# LM5116.net
KiCad netlist of a schematic drawn in Altium Designer
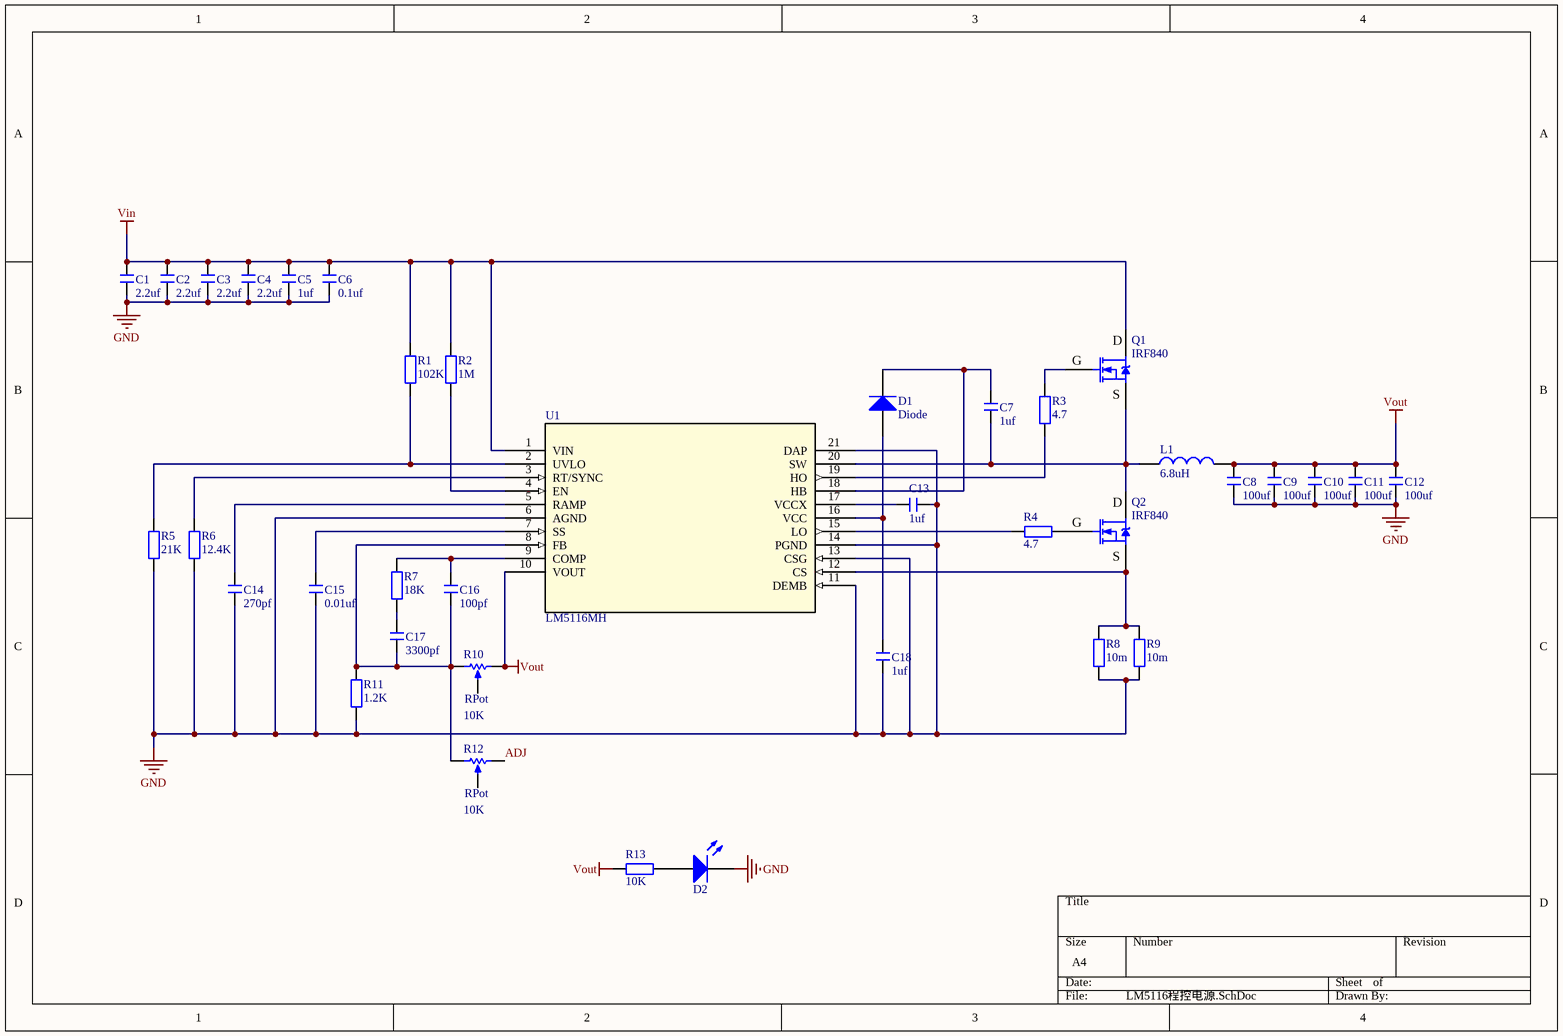
[diagram p0: LM5116程控电源.SchDoc]

(export (version "E")
  (design (tool "Eeschema 10.0.6"))
  (components
    (comp (ref "C1")
      (value "2.2uf")
      (footprint "C 1812_L")
      (description "贴片电容")
      (libsource (lib "0.1 - 电阻-电容-电感") (part "C"))
    )
    (comp (ref "C2")
      (value "2.2uf")
      (footprint "C 1812_L")
      (description "贴片电容")
      (libsource (lib "0.1 - 电阻-电容-电感") (part "C"))
    )
    (comp (ref "C3")
      (value "2.2uf")
      (footprint "C 1812_L")
      (description "贴片电容")
      (libsource (lib "0.1 - 电阻-电容-电感") (part "C"))
    )
    (comp (ref "C4")
      (value "2.2uf")
      (footprint "C 1812_L")
      (description "贴片电容")
      (libsource (lib "0.1 - 电阻-电容-电感") (part "C"))
    )
    (comp (ref "C5")
      (value "1uf")
      (footprint "C 1210_L")
      (description "贴片电容")
      (libsource (lib "0.1 - 电阻-电容-电感") (part "C"))
    )
    (comp (ref "C6")
      (value "0.1uf")
      (footprint "C 0805_L")
      (description "贴片电容")
      (libsource (lib "0.1 - 电阻-电容-电感") (part "C"))
    )
    (comp (ref "C7")
      (value "1uf")
      (footprint "C 0805_L")
      (description "贴片电容")
      (libsource (lib "0.1 - 电阻-电容-电感") (part "C"))
    )
    (comp (ref "C8")
      (value "100uf")
      (footprint "C 1812_L")
      (description "贴片电容")
      (libsource (lib "0.1 - 电阻-电容-电感") (part "C"))
    )
    (comp (ref "C9")
      (value "100uf")
      (footprint "C 1812_L")
      (description "贴片电容")
      (libsource (lib "0.1 - 电阻-电容-电感") (part "C"))
    )
    (comp (ref "C10")
      (value "100uf")
      (footprint "C 1812_L")
      (description "贴片电容")
      (libsource (lib "0.1 - 电阻-电容-电感") (part "C"))
    )
    (comp (ref "C11")
      (value "100uf")
      (footprint "C 1812_L")
      (description "贴片电容")
      (libsource (lib "0.1 - 电阻-电容-电感") (part "C"))
    )
    (comp (ref "C12")
      (value "100uf")
      (footprint "C 1812_L")
      (description "贴片电容")
      (libsource (lib "0.1 - 电阻-电容-电感") (part "C"))
    )
    (comp (ref "C13")
      (value "1uf")
      (footprint "C 0805_L")
      (description "贴片电容")
      (libsource (lib "0.1 - 电阻-电容-电感") (part "C"))
    )
    (comp (ref "C14")
      (value "270pf")
      (footprint "C 0603_L")
      (description "贴片电容")
      (libsource (lib "0.1 - 电阻-电容-电感") (part "C"))
    )
    (comp (ref "C15")
      (value "0.01uf")
      (footprint "C 0603_L")
      (description "贴片电容")
      (libsource (lib "0.1 - 电阻-电容-电感") (part "C"))
    )
    (comp (ref "C16")
      (value "100pf")
      (footprint "C 0603_L")
      (description "贴片电容")
      (libsource (lib "0.1 - 电阻-电容-电感") (part "C"))
    )
    (comp (ref "C17")
      (value "3300pf")
      (footprint "C 0603_L")
      (description "贴片电容")
      (libsource (lib "0.1 - 电阻-电容-电感") (part "C"))
    )
    (comp (ref "C18")
      (value "1uf")
      (footprint "C 0805_L")
      (description "贴片电容")
      (libsource (lib "0.1 - 电阻-电容-电感") (part "C"))
    )
    (comp (ref "D1")
      (value "Diode")
      (footprint "1.30-二极管-整流桥堆:SOD-323")
      (description "Default Diode")
      (fields (field (name "PUBLISHER") "Altium Limited"))
      (libsource (lib "Miscellaneous Devices") (part "Diode"))
    )
    (comp (ref "D2")
      (value "LED")
      (footprint "LED 0603G")
      (description "发光二极管")
      (libsource (lib "0.3 - LED发光二极管") (part "LED"))
    )
    (comp (ref "L1")
      (value "6.8uH")
      (footprint "IND-SMD_L12.6-W12.6_MS1350-XX")
      (description "小功率贴片电感")
      (libsource (lib "0.1 - 电阻-电容-电感") (part "L"))
    )
    (comp (ref "Q1")
      (value "IRF840")
      (footprint "SOT669")
      (description "N沟场效应管")
      (libsource (lib "0.5 - 场效应管-可控硅") (part "IRF840"))
    )
    (comp (ref "Q2")
      (value "IRF840")
      (footprint "SOT669")
      (description "N沟场效应管")
      (libsource (lib "0.5 - 场效应管-可控硅") (part "IRF840"))
    )
    (comp (ref "R1")
      (value "102K")
      (footprint "R 0603_L")
      (description "贴片电阻")
      (fields (field (name "版权归属") "来自淘宝 ID：黄晶宝石"))
      (libsource (lib "0.1 - 电阻-电容-电感") (part "R"))
    )
    (comp (ref "R2")
      (value "1M")
      (footprint "R 0603_L")
      (description "贴片电阻")
      (fields (field (name "版权归属") "来自淘宝 ID：黄晶宝石"))
      (libsource (lib "0.1 - 电阻-电容-电感") (part "R"))
    )
    (comp (ref "R3")
      (value "4.7")
      (footprint "R 0603_L")
      (description "贴片电阻")
      (fields (field (name "版权归属") "来自淘宝 ID：黄晶宝石"))
      (libsource (lib "0.1 - 电阻-电容-电感") (part "R"))
    )
    (comp (ref "R4")
      (value "4.7")
      (footprint "R 0603_L")
      (description "贴片电阻")
      (fields (field (name "版权归属") "来自淘宝 ID：黄晶宝石"))
      (libsource (lib "0.1 - 电阻-电容-电感") (part "R"))
    )
    (comp (ref "R5")
      (value "21K")
      (footprint "R 0603_L")
      (description "贴片电阻")
      (fields (field (name "版权归属") "来自淘宝 ID：黄晶宝石"))
      (libsource (lib "0.1 - 电阻-电容-电感") (part "R"))
    )
    (comp (ref "R6")
      (value "12.4K")
      (footprint "R 0603_L")
      (description "贴片电阻")
      (fields (field (name "版权归属") "来自淘宝 ID：黄晶宝石"))
      (libsource (lib "0.1 - 电阻-电容-电感") (part "R"))
    )
    (comp (ref "R7")
      (value "18K")
      (footprint "R 0603_L")
      (description "贴片电阻")
      (fields (field (name "版权归属") "来自淘宝 ID：黄晶宝石"))
      (libsource (lib "0.1 - 电阻-电容-电感") (part "R"))
    )
    (comp (ref "R8")
      (value "10m")
      (footprint "R 0805_L")
      (description "贴片电阻")
      (fields (field (name "版权归属") "来自淘宝 ID：黄晶宝石"))
      (libsource (lib "0.1 - 电阻-电容-电感") (part "R"))
    )
    (comp (ref "R9")
      (value "10m")
      (footprint "R 0805_L")
      (description "贴片电阻")
      (fields (field (name "版权归属") "来自淘宝 ID：黄晶宝石"))
      (libsource (lib "0.1 - 电阻-电容-电感") (part "R"))
    )
    (comp (ref "R10")
      (value "RPot")
      (footprint "RES-ADJ-SMD_3P-L3.8-W3.6-P1.90-BL")
      (description "Potentiometer")
      (fields (field (name "ALTIUM_VALUE") "10K") (field (name "PUBLISHER") "Altium Limited"))
      (libsource (lib "Miscellaneous Devices") (part "RPot"))
    )
    (comp (ref "R11")
      (value "1.2K")
      (footprint "R 0603_L")
      (description "贴片电阻")
      (fields (field (name "版权归属") "来自淘宝 ID：黄晶宝石"))
      (libsource (lib "0.1 - 电阻-电容-电感") (part "R"))
    )
    (comp (ref "R12")
      (value "RPot")
      (footprint "RES-ADJ-SMD_3P-L3.8-W3.6-P1.90-BL")
      (description "Potentiometer")
      (fields (field (name "ALTIUM_VALUE") "10K") (field (name "PUBLISHER") "Altium Limited"))
      (libsource (lib "Miscellaneous Devices") (part "RPot"))
    )
    (comp (ref "R13")
      (value "10K")
      (footprint "R 0603_L")
      (description "贴片电阻")
      (fields (field (name "版权归属") "来自淘宝 ID：黄晶宝石"))
      (libsource (lib "0.1 - 电阻-电容-电感") (part "R"))
    )
    (comp (ref "U1")
      (value "LM5116MH")
      (footprint "HTSSOP-20_L6.5-W4.4-P0.65-LS6.4-BL-EP")
      (description "No Description Available")
      (fields (field (name "COPYRIGHT") "Copyright (C) 2024 Ultra Librarian. All rights reserved."))
      (libsource (lib "LM5116MH") (part "LM5116MH"))
    )
  )
  (nets
    (net (code "1") (name "/ADJ") (class "Default")
      (node (ref "R12") (pin "2") (pinfunction "BOT_2") (pintype "passive"))
    )
    (net (code "2") (name "GND") (class "Default")
      (node (ref "C1") (pin "1") (pinfunction "1_1") (pintype "passive"))
      (node (ref "C10") (pin "1") (pinfunction "1_1") (pintype "passive"))
      (node (ref "C11") (pin "1") (pinfunction "1_1") (pintype "passive"))
      (node (ref "C12") (pin "1") (pinfunction "1_1") (pintype "passive"))
      (node (ref "C13") (pin "1") (pinfunction "1_1") (pintype "passive"))
      (node (ref "C14") (pin "1") (pinfunction "1_1") (pintype "passive"))
      (node (ref "C15") (pin "1") (pinfunction "1_1") (pintype "passive"))
      (node (ref "C18") (pin "1") (pinfunction "1_1") (pintype "passive"))
      (node (ref "C2") (pin "1") (pinfunction "1_1") (pintype "passive"))
      (node (ref "C3") (pin "1") (pinfunction "1_1") (pintype "passive"))
      (node (ref "C4") (pin "1") (pinfunction "1_1") (pintype "passive"))
      (node (ref "C5") (pin "1") (pinfunction "1_1") (pintype "passive"))
      (node (ref "C6") (pin "1") (pinfunction "1_1") (pintype "passive"))
      (node (ref "C8") (pin "1") (pinfunction "1_1") (pintype "passive"))
      (node (ref "C9") (pin "1") (pinfunction "1_1") (pintype "passive"))
      (node (ref "D2") (pin "2") (pinfunction "K_2") (pintype "passive"))
      (node (ref "R11") (pin "1") (pinfunction "1_1") (pintype "passive"))
      (node (ref "R5") (pin "1") (pinfunction "1_1") (pintype "passive"))
      (node (ref "R6") (pin "1") (pinfunction "1_1") (pintype "passive"))
      (node (ref "R8") (pin "1") (pinfunction "1_1") (pintype "passive"))
      (node (ref "R9") (pin "1") (pinfunction "1_1") (pintype "passive"))
      (node (ref "U1") (pin "11") (pinfunction "DEMB_11") (pintype "input"))
      (node (ref "U1") (pin "13") (pinfunction "CSG_13") (pintype "input"))
      (node (ref "U1") (pin "14") (pinfunction "PGND_14") (pintype "power_in"))
      (node (ref "U1") (pin "21") (pinfunction "DAP_21") (pintype "power_in"))
      (node (ref "U1") (pin "6") (pinfunction "AGND_6") (pintype "power_in"))
    )
    (net (code "3") (name "Net-(C17-Pad2)") (class "Default")
      (node (ref "C17") (pin "2") (pinfunction "2_2") (pintype "passive"))
      (node (ref "R7") (pin "1") (pinfunction "1_1") (pintype "passive"))
    )
    (net (code "4") (name "Net-(D1-A)") (class "Default")
      (node (ref "C18") (pin "2") (pinfunction "2_2") (pintype "passive"))
      (node (ref "D1") (pin "1") (pinfunction "A_1") (pintype "passive"))
      (node (ref "U1") (pin "16") (pinfunction "VCC_16") (pintype "power_in"))
    )
    (net (code "5") (name "Net-(D1-K)") (class "Default")
      (node (ref "C7") (pin "2") (pinfunction "2_2") (pintype "passive"))
      (node (ref "D1") (pin "2") (pinfunction "K_2") (pintype "passive"))
      (node (ref "U1") (pin "18") (pinfunction "HB_18") (pintype "passive"))
    )
    (net (code "6") (name "Net-(D2-A)") (class "Default")
      (node (ref "D2") (pin "1") (pinfunction "A_1") (pintype "passive"))
      (node (ref "R13") (pin "1") (pinfunction "1_1") (pintype "passive"))
    )
    (net (code "7") (name "Net-(Q1-G)") (class "Default")
      (node (ref "Q1") (pin "1") (pinfunction "G_1") (pintype "passive"))
      (node (ref "R3") (pin "2") (pinfunction "2_2") (pintype "passive"))
    )
    (net (code "8") (name "Net-(Q1-S)") (class "Default")
      (node (ref "C7") (pin "1") (pinfunction "1_1") (pintype "passive"))
      (node (ref "L1") (pin "1") (pinfunction "1_1") (pintype "passive"))
      (node (ref "Q1") (pin "3") (pinfunction "S_3") (pintype "passive"))
      (node (ref "Q2") (pin "2") (pinfunction "D_2") (pintype "passive"))
      (node (ref "U1") (pin "20") (pinfunction "SW_20") (pintype "power_in"))
    )
    (net (code "9") (name "Net-(Q2-G)") (class "Default")
      (node (ref "Q2") (pin "1") (pinfunction "G_1") (pintype "passive"))
      (node (ref "R4") (pin "1") (pinfunction "1_1") (pintype "passive"))
    )
    (net (code "10") (name "Net-(Q2-S)") (class "Default")
      (node (ref "Q2") (pin "3") (pinfunction "S_3") (pintype "passive"))
      (node (ref "R8") (pin "2") (pinfunction "2_2") (pintype "passive"))
      (node (ref "R9") (pin "2") (pinfunction "2_2") (pintype "passive"))
      (node (ref "U1") (pin "12") (pinfunction "CS_12") (pintype "input"))
    )
    (net (code "11") (name "Net-(R10-TOP)") (class "Default")
      (node (ref "C16") (pin "1") (pinfunction "1_1") (pintype "passive"))
      (node (ref "C17") (pin "1") (pinfunction "1_1") (pintype "passive"))
      (node (ref "R10") (pin "1") (pinfunction "TOP_1") (pintype "passive"))
      (node (ref "R11") (pin "2") (pinfunction "2_2") (pintype "passive"))
      (node (ref "R12") (pin "1") (pinfunction "TOP_1") (pintype "passive"))
      (node (ref "U1") (pin "8") (pinfunction "FB_8") (pintype "input"))
    )
    (net (code "12") (name "Net-(U1-COMP)") (class "Default")
      (node (ref "C16") (pin "2") (pinfunction "2_2") (pintype "passive"))
      (node (ref "R7") (pin "2") (pinfunction "2_2") (pintype "passive"))
      (node (ref "U1") (pin "9") (pinfunction "COMP_9") (pintype "passive"))
    )
    (net (code "13") (name "Net-(U1-EN)") (class "Default")
      (node (ref "R2") (pin "1") (pinfunction "1_1") (pintype "passive"))
      (node (ref "U1") (pin "4") (pinfunction "EN_4") (pintype "input"))
    )
    (net (code "14") (name "Net-(U1-HO)") (class "Default")
      (node (ref "R3") (pin "1") (pinfunction "1_1") (pintype "passive"))
      (node (ref "U1") (pin "19") (pinfunction "HO_19") (pintype "output"))
    )
    (net (code "15") (name "Net-(U1-LO)") (class "Default")
      (node (ref "R4") (pin "2") (pinfunction "2_2") (pintype "passive"))
      (node (ref "U1") (pin "15") (pinfunction "LO_15") (pintype "output"))
    )
    (net (code "16") (name "Net-(U1-RAMP)") (class "Default")
      (node (ref "C14") (pin "2") (pinfunction "2_2") (pintype "passive"))
      (node (ref "U1") (pin "5") (pinfunction "RAMP_5") (pintype "passive"))
    )
    (net (code "17") (name "Net-(U1-RT{slash}SYNC)") (class "Default")
      (node (ref "R6") (pin "2") (pinfunction "2_2") (pintype "passive"))
      (node (ref "U1") (pin "3") (pinfunction "RT/SYNC_3") (pintype "input"))
    )
    (net (code "18") (name "Net-(U1-SS)") (class "Default")
      (node (ref "C15") (pin "2") (pinfunction "2_2") (pintype "passive"))
      (node (ref "U1") (pin "7") (pinfunction "SS_7") (pintype "input"))
    )
    (net (code "19") (name "Net-(U1-UVLO)") (class "Default")
      (node (ref "R1") (pin "1") (pinfunction "1_1") (pintype "passive"))
      (node (ref "R5") (pin "2") (pinfunction "2_2") (pintype "passive"))
      (node (ref "U1") (pin "2") (pinfunction "UVLO_2") (pintype "passive"))
    )
    (net (code "20") (name "Net-(U1-VCCX)") (class "Default")
      (node (ref "C13") (pin "2") (pinfunction "2_2") (pintype "passive"))
      (node (ref "U1") (pin "17") (pinfunction "VCCX_17") (pintype "power_in"))
    )
    (net (code "21") (name "Vin") (class "Default")
      (node (ref "C1") (pin "2") (pinfunction "2_2") (pintype "passive"))
      (node (ref "C2") (pin "2") (pinfunction "2_2") (pintype "passive"))
      (node (ref "C3") (pin "2") (pinfunction "2_2") (pintype "passive"))
      (node (ref "C4") (pin "2") (pinfunction "2_2") (pintype "passive"))
      (node (ref "C5") (pin "2") (pinfunction "2_2") (pintype "passive"))
      (node (ref "C6") (pin "2") (pinfunction "2_2") (pintype "passive"))
      (node (ref "Q1") (pin "2") (pinfunction "D_2") (pintype "passive"))
      (node (ref "R1") (pin "2") (pinfunction "2_2") (pintype "passive"))
      (node (ref "R2") (pin "2") (pinfunction "2_2") (pintype "passive"))
      (node (ref "U1") (pin "1") (pinfunction "VIN_1") (pintype "power_in"))
    )
    (net (code "22") (name "Vout") (class "Default")
      (node (ref "C10") (pin "2") (pinfunction "2_2") (pintype "passive"))
      (node (ref "C11") (pin "2") (pinfunction "2_2") (pintype "passive"))
      (node (ref "C12") (pin "2") (pinfunction "2_2") (pintype "passive"))
      (node (ref "C8") (pin "2") (pinfunction "2_2") (pintype "passive"))
      (node (ref "C9") (pin "2") (pinfunction "2_2") (pintype "passive"))
      (node (ref "L1") (pin "2") (pinfunction "2_2") (pintype "passive"))
      (node (ref "R10") (pin "2") (pinfunction "BOT_2") (pintype "passive"))
      (node (ref "R13") (pin "2") (pinfunction "2_2") (pintype "passive"))
      (node (ref "U1") (pin "10") (pinfunction "VOUT_10") (pintype "passive"))
    )
    (net (code "23") (name "unconnected-(R10-TAP-Pad3)") (class "Default")
      (node (ref "R10") (pin "3") (pinfunction "TAP_3") (pintype "passive"))
    )
    (net (code "24") (name "unconnected-(R12-TAP-Pad3)") (class "Default")
      (node (ref "R12") (pin "3") (pinfunction "TAP_3") (pintype "passive"))
    )
  )
)
